# 22-TimingConnections.net
KiCad netlist of a schematic drawn in Altium Designer
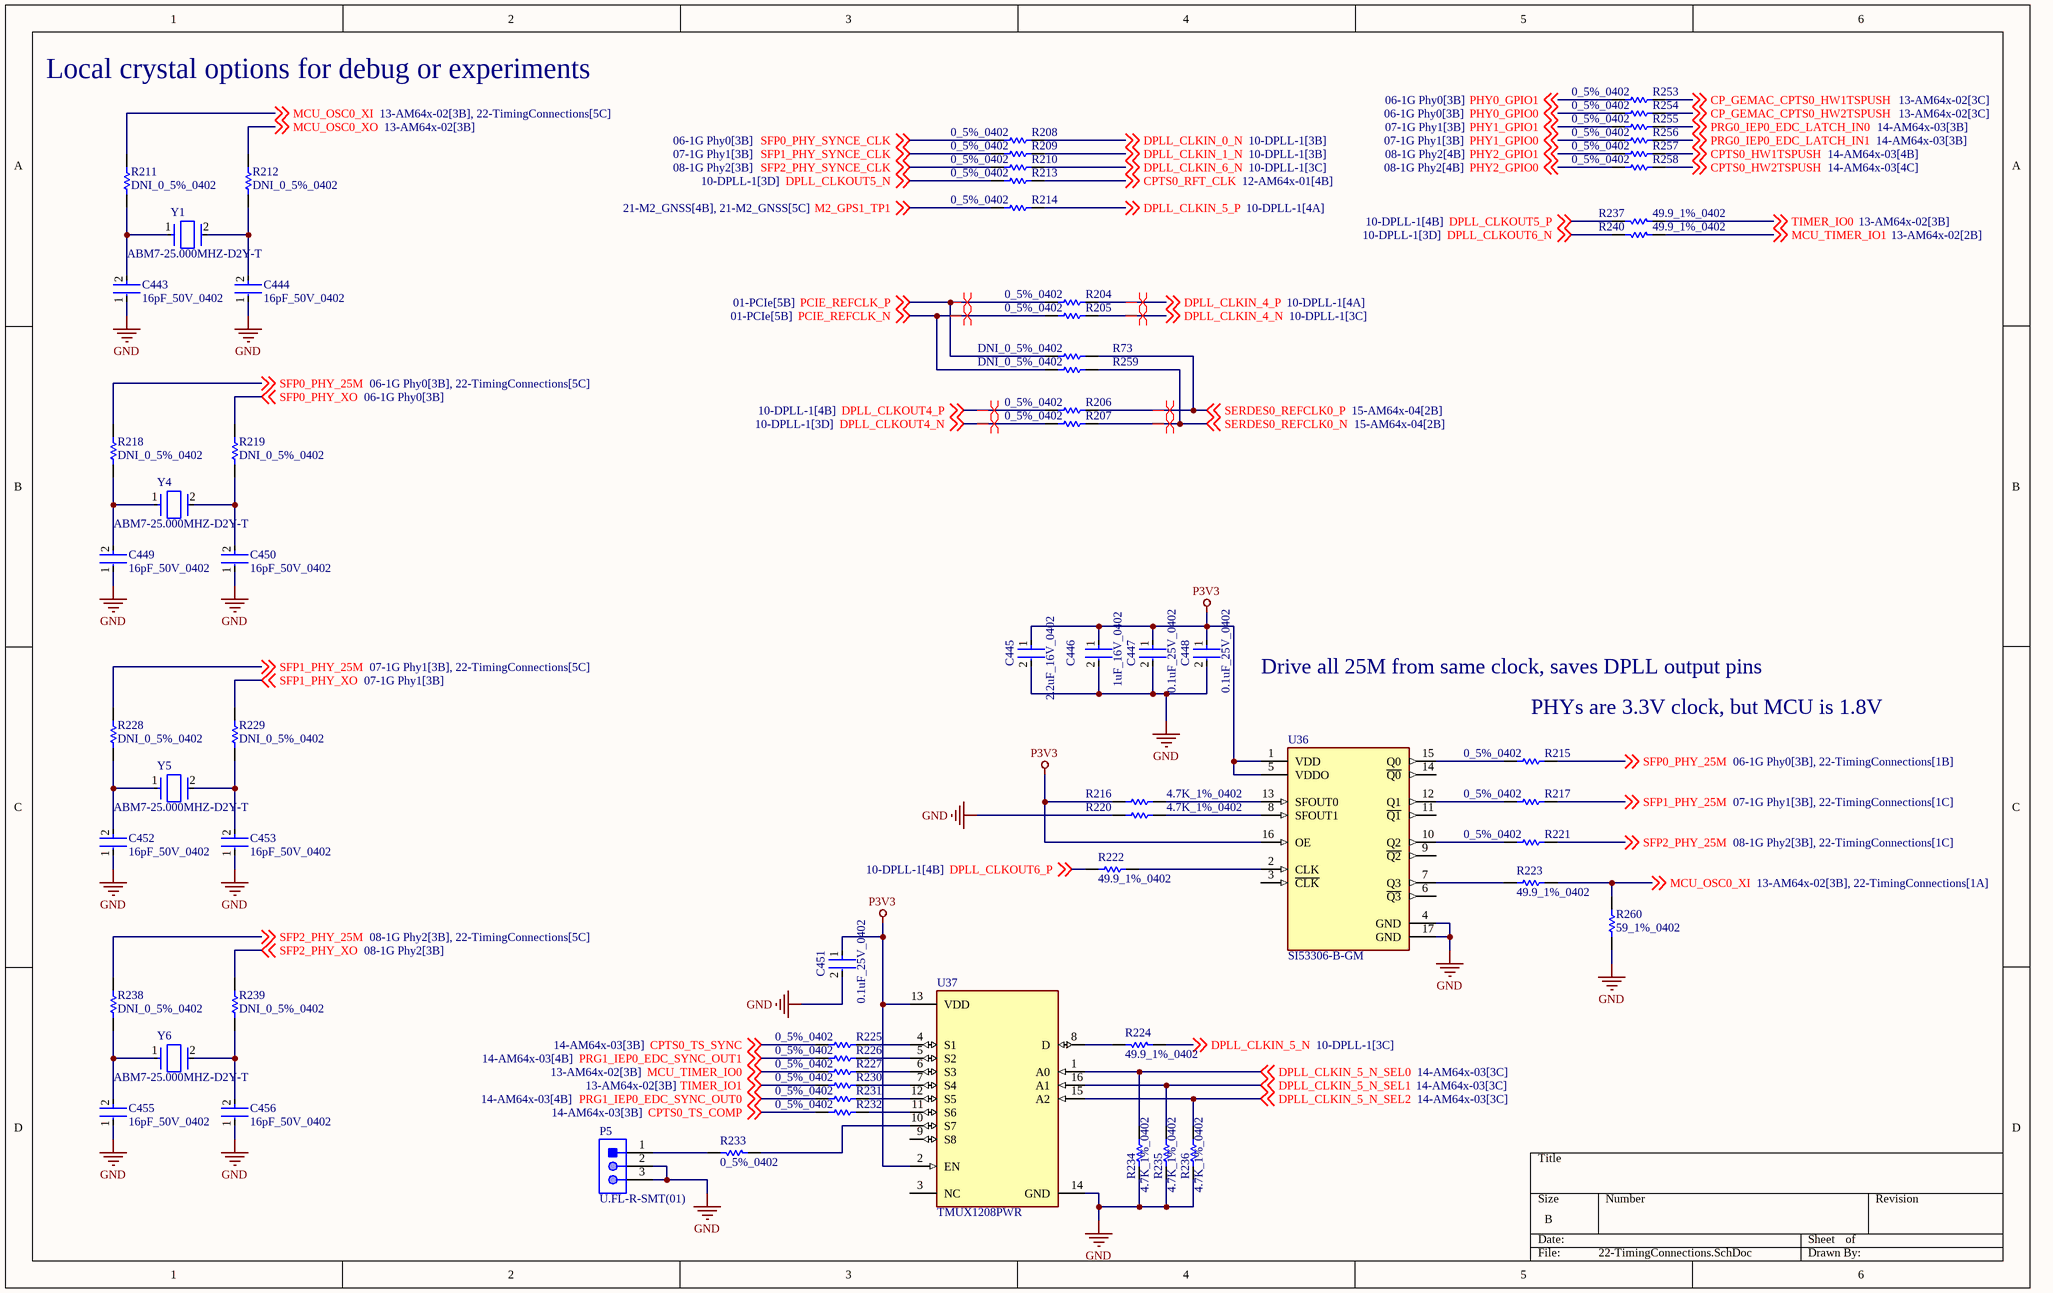
[diagram p0: 22-TimingConnections.SchDoc]

(export (version "E")
  (design (tool "Eeschema 10.0.6"))
  (components
    (comp (ref "C443")
      (value "16pF_50V_0402")
      (footprint "FP-CBR04C-MFG")
      (description "CAP CER 16PF 50V C0G/NP0 0402")
      (fields (field (name "MANUFACTURER") "KEMET") (field (name "TOLERANCE") "0.05"))
      (libsource (lib "Altium Content Vault") (part "236180d848d6139a670b325ea6854c9"))
    )
    (comp (ref "C444")
      (value "16pF_50V_0402")
      (footprint "FP-CBR04C-MFG")
      (description "CAP CER 16PF 50V C0G/NP0 0402")
      (fields (field (name "MANUFACTURER") "KEMET") (field (name "TOLERANCE") "0.05"))
      (libsource (lib "Altium Content Vault") (part "236180d848d6139a670b325ea6854c9"))
    )
    (comp (ref "C445")
      (value "2.2uF_16V_0402")
      (footprint "FP-C1005-050-0_05-IPC_A")
      (description "Multilayer Ceramic Capacitors 2.2μF ±10% 16V X5R SMD 0402")
      (fields (field (name "TOLERANCE") "10%"))
      (libsource (lib "Altium Content Vault") (part "b4654b650e69147ec39a6b967a45e02"))
    )
    (comp (ref "C446")
      (value "1uF_16V_0402")
      (footprint "FP-0402-L_1_0_0_05-W_0_5-IPC_A")
      (description "None")
      (fields (field (name "TOLERANCE") "10%"))
      (libsource (lib "Altium Content Vault") (part "b4654b650e69147ec39a6b967a45e02"))
    )
    (comp (ref "C447")
      (value "0.1uF_25V_0402")
      (footprint "FP-0402-L_1_0_1-W_0_5_0_1-IPC_C")
      (description "General Purpose Ceramic Capacitor, 0402, 100nF, 10%, X7R, 15%, 25V")
      (fields (field (name "VOLTAGE") "25V") (field (name "TOLERANCE") "10%"))
      (libsource (lib "Altium Content Vault") (part "b4654b650e69147ec39a6b967a45e02"))
    )
    (comp (ref "C448")
      (value "0.1uF_25V_0402")
      (footprint "FP-0402-L_1_0_1-W_0_5_0_1-IPC_C")
      (description "General Purpose Ceramic Capacitor, 0402, 100nF, 10%, X7R, 15%, 25V")
      (fields (field (name "VOLTAGE") "25V") (field (name "TOLERANCE") "10%"))
      (libsource (lib "Altium Content Vault") (part "b4654b650e69147ec39a6b967a45e02"))
    )
    (comp (ref "C449")
      (value "16pF_50V_0402")
      (footprint "FP-CBR04C-MFG")
      (description "CAP CER 16PF 50V C0G/NP0 0402")
      (fields (field (name "MANUFACTURER") "KEMET") (field (name "TOLERANCE") "0.05"))
      (libsource (lib "Altium Content Vault") (part "236180d848d6139a670b325ea6854c9"))
    )
    (comp (ref "C450")
      (value "16pF_50V_0402")
      (footprint "FP-CBR04C-MFG")
      (description "CAP CER 16PF 50V C0G/NP0 0402")
      (fields (field (name "MANUFACTURER") "KEMET") (field (name "TOLERANCE") "0.05"))
      (libsource (lib "Altium Content Vault") (part "236180d848d6139a670b325ea6854c9"))
    )
    (comp (ref "C451")
      (value "0.1uF_25V_0402")
      (footprint "FP-0402-L_1_0_1-W_0_5_0_1-IPC_C")
      (description "General Purpose Ceramic Capacitor, 0402, 100nF, 10%, X7R, 15%, 25V")
      (fields (field (name "VOLTAGE") "25V") (field (name "TOLERANCE") "10%"))
      (libsource (lib "Altium Content Vault") (part "b4654b650e69147ec39a6b967a45e02"))
    )
    (comp (ref "C452")
      (value "16pF_50V_0402")
      (footprint "FP-CBR04C-MFG")
      (description "CAP CER 16PF 50V C0G/NP0 0402")
      (fields (field (name "MANUFACTURER") "KEMET") (field (name "TOLERANCE") "0.05"))
      (libsource (lib "Altium Content Vault") (part "236180d848d6139a670b325ea6854c9"))
    )
    (comp (ref "C453")
      (value "16pF_50V_0402")
      (footprint "FP-CBR04C-MFG")
      (description "CAP CER 16PF 50V C0G/NP0 0402")
      (fields (field (name "MANUFACTURER") "KEMET") (field (name "TOLERANCE") "0.05"))
      (libsource (lib "Altium Content Vault") (part "236180d848d6139a670b325ea6854c9"))
    )
    (comp (ref "C455")
      (value "16pF_50V_0402")
      (footprint "FP-CBR04C-MFG")
      (description "CAP CER 16PF 50V C0G/NP0 0402")
      (fields (field (name "MANUFACTURER") "KEMET") (field (name "TOLERANCE") "0.05"))
      (libsource (lib "Altium Content Vault") (part "236180d848d6139a670b325ea6854c9"))
    )
    (comp (ref "C456")
      (value "16pF_50V_0402")
      (footprint "FP-CBR04C-MFG")
      (description "CAP CER 16PF 50V C0G/NP0 0402")
      (fields (field (name "MANUFACTURER") "KEMET") (field (name "TOLERANCE") "0.05"))
      (libsource (lib "Altium Content Vault") (part "236180d848d6139a670b325ea6854c9"))
    )
    (comp (ref "P5")
      (value "U.FL-R-SMT(01)")
      (footprint "HRS-U.FL-R-SMT(10)_V")
      (description "CONN RECPT ULTRA-MINI COAX SMD")
      (fields (field (name "MANUFACTURER") "Hirose Electric") (field (name "APPROVAL CATEGORY") "UL94V-0"))
      (libsource (lib "Altium Content Vault") (part "CN-1P-M-R3"))
    )
    (comp (ref "R73")
      (value "DNI_0_5%_0402")
      (footprint "RESC1005X40X25LL10T10")
      (fields (field (name "MANUFACTURER") "KOA Speer") (field (name "PART NUMBER") "RK73Z1ETTP"))
      (libsource (lib "Altium Content Vault") (part "RES"))
    )
    (comp (ref "R204")
      (value "0_5%_0402")
      (footprint "RESC1005X40X25LL10T10")
      (fields (field (name "MANUFACTURER") "KOA Speer") (field (name "PART NUMBER") "RK73Z1ETTP"))
      (libsource (lib "Altium Content Vault") (part "RES"))
    )
    (comp (ref "R205")
      (value "0_5%_0402")
      (footprint "RESC1005X40X25LL10T10")
      (fields (field (name "MANUFACTURER") "KOA Speer") (field (name "PART NUMBER") "RK73Z1ETTP"))
      (libsource (lib "Altium Content Vault") (part "RES"))
    )
    (comp (ref "R206")
      (value "0_5%_0402")
      (footprint "RESC1005X40X25LL10T10")
      (fields (field (name "MANUFACTURER") "KOA Speer") (field (name "PART NUMBER") "RK73Z1ETTP"))
      (libsource (lib "Altium Content Vault") (part "RES"))
    )
    (comp (ref "R207")
      (value "0_5%_0402")
      (footprint "RESC1005X40X25LL10T10")
      (fields (field (name "MANUFACTURER") "KOA Speer") (field (name "PART NUMBER") "RK73Z1ETTP"))
      (libsource (lib "Altium Content Vault") (part "RES"))
    )
    (comp (ref "R208")
      (value "0_5%_0402")
      (footprint "RESC1005X40X25LL10T10")
      (fields (field (name "MANUFACTURER") "KOA Speer") (field (name "PART NUMBER") "RK73Z1ETTP"))
      (libsource (lib "Altium Content Vault") (part "RES"))
    )
    (comp (ref "R209")
      (value "0_5%_0402")
      (footprint "RESC1005X40X25LL10T10")
      (fields (field (name "MANUFACTURER") "KOA Speer") (field (name "PART NUMBER") "RK73Z1ETTP"))
      (libsource (lib "Altium Content Vault") (part "RES"))
    )
    (comp (ref "R210")
      (value "0_5%_0402")
      (footprint "RESC1005X40X25LL10T10")
      (fields (field (name "MANUFACTURER") "KOA Speer") (field (name "PART NUMBER") "RK73Z1ETTP"))
      (libsource (lib "Altium Content Vault") (part "RES"))
    )
    (comp (ref "R211")
      (value "DNI_0_5%_0402")
      (footprint "RESC1005X40X25LL10T10")
      (fields (field (name "MANUFACTURER") "KOA Speer") (field (name "PART NUMBER") "RK73Z1ETTP"))
      (libsource (lib "Altium Content Vault") (part "RES"))
    )
    (comp (ref "R212")
      (value "DNI_0_5%_0402")
      (footprint "RESC1005X40X25LL10T10")
      (fields (field (name "MANUFACTURER") "KOA Speer") (field (name "PART NUMBER") "RK73Z1ETTP"))
      (libsource (lib "Altium Content Vault") (part "RES"))
    )
    (comp (ref "R213")
      (value "0_5%_0402")
      (footprint "RESC1005X40X25LL10T10")
      (fields (field (name "MANUFACTURER") "KOA Speer") (field (name "PART NUMBER") "RK73Z1ETTP"))
      (libsource (lib "Altium Content Vault") (part "RES"))
    )
    (comp (ref "R214")
      (value "0_5%_0402")
      (footprint "RESC1005X40X25LL10T10")
      (fields (field (name "MANUFACTURER") "KOA Speer") (field (name "PART NUMBER") "RK73Z1ETTP"))
      (libsource (lib "Altium Content Vault") (part "RES"))
    )
    (comp (ref "R215")
      (value "0_5%_0402")
      (footprint "RESC1005X40X25LL10T10")
      (fields (field (name "MANUFACTURER") "KOA Speer") (field (name "PART NUMBER") "RK73Z1ETTP"))
      (libsource (lib "Altium Content Vault") (part "RES"))
    )
    (comp (ref "R216")
      (value "4.7K_1%_0402")
      (footprint "RESC1005X40X25NL10T10")
      (fields (field (name "MANUFACTURER") "Bourns") (field (name "PART NUMBER") "CR0402-FX-4701GLF"))
      (libsource (lib "Altium Content Vault") (part "RES"))
    )
    (comp (ref "R217")
      (value "0_5%_0402")
      (footprint "RESC1005X40X25LL10T10")
      (fields (field (name "MANUFACTURER") "KOA Speer") (field (name "PART NUMBER") "RK73Z1ETTP"))
      (libsource (lib "Altium Content Vault") (part "RES"))
    )
    (comp (ref "R218")
      (value "DNI_0_5%_0402")
      (footprint "RESC1005X40X25LL10T10")
      (fields (field (name "MANUFACTURER") "KOA Speer") (field (name "PART NUMBER") "RK73Z1ETTP"))
      (libsource (lib "Altium Content Vault") (part "RES"))
    )
    (comp (ref "R219")
      (value "DNI_0_5%_0402")
      (footprint "RESC1005X40X25LL10T10")
      (fields (field (name "MANUFACTURER") "KOA Speer") (field (name "PART NUMBER") "RK73Z1ETTP"))
      (libsource (lib "Altium Content Vault") (part "RES"))
    )
    (comp (ref "R220")
      (value "4.7K_1%_0402")
      (footprint "RESC1005X40X25NL10T10")
      (fields (field (name "MANUFACTURER") "Bourns") (field (name "PART NUMBER") "CR0402-FX-4701GLF"))
      (libsource (lib "Altium Content Vault") (part "RES"))
    )
    (comp (ref "R221")
      (value "0_5%_0402")
      (footprint "RESC1005X40X25LL10T10")
      (fields (field (name "MANUFACTURER") "KOA Speer") (field (name "PART NUMBER") "RK73Z1ETTP"))
      (libsource (lib "Altium Content Vault") (part "RES"))
    )
    (comp (ref "R222")
      (value "49.9_1%_0402")
      (footprint "RESC1005X40X25NL10T10")
      (fields (field (name "PART NUMBER") "RK73H1ETTP49R9F") (field (name "MANUFACTURER") "KOA Speer"))
      (libsource (lib "Altium Content Vault") (part "RES"))
    )
    (comp (ref "R223")
      (value "49.9_1%_0402")
      (footprint "RESC1005X40X25NL10T10")
      (fields (field (name "PART NUMBER") "RK73H1ETTP49R9F") (field (name "MANUFACTURER") "KOA Speer"))
      (libsource (lib "Altium Content Vault") (part "RES"))
    )
    (comp (ref "R224")
      (value "49.9_1%_0402")
      (footprint "RESC1005X40X25NL10T10")
      (fields (field (name "PART NUMBER") "RK73H1ETTP49R9F") (field (name "MANUFACTURER") "KOA Speer"))
      (libsource (lib "Altium Content Vault") (part "RES"))
    )
    (comp (ref "R225")
      (value "0_5%_0402")
      (footprint "RESC1005X40X25LL10T10")
      (fields (field (name "MANUFACTURER") "KOA Speer") (field (name "PART NUMBER") "RK73Z1ETTP"))
      (libsource (lib "Altium Content Vault") (part "RES"))
    )
    (comp (ref "R226")
      (value "0_5%_0402")
      (footprint "RESC1005X40X25LL10T10")
      (fields (field (name "MANUFACTURER") "KOA Speer") (field (name "PART NUMBER") "RK73Z1ETTP"))
      (libsource (lib "Altium Content Vault") (part "RES"))
    )
    (comp (ref "R227")
      (value "0_5%_0402")
      (footprint "RESC1005X40X25LL10T10")
      (fields (field (name "MANUFACTURER") "KOA Speer") (field (name "PART NUMBER") "RK73Z1ETTP"))
      (libsource (lib "Altium Content Vault") (part "RES"))
    )
    (comp (ref "R228")
      (value "DNI_0_5%_0402")
      (footprint "RESC1005X40X25LL10T10")
      (fields (field (name "MANUFACTURER") "KOA Speer") (field (name "PART NUMBER") "RK73Z1ETTP"))
      (libsource (lib "Altium Content Vault") (part "RES"))
    )
    (comp (ref "R229")
      (value "DNI_0_5%_0402")
      (footprint "RESC1005X40X25LL10T10")
      (fields (field (name "MANUFACTURER") "KOA Speer") (field (name "PART NUMBER") "RK73Z1ETTP"))
      (libsource (lib "Altium Content Vault") (part "RES"))
    )
    (comp (ref "R230")
      (value "0_5%_0402")
      (footprint "RESC1005X40X25LL10T10")
      (fields (field (name "MANUFACTURER") "KOA Speer") (field (name "PART NUMBER") "RK73Z1ETTP"))
      (libsource (lib "Altium Content Vault") (part "RES"))
    )
    (comp (ref "R231")
      (value "0_5%_0402")
      (footprint "RESC1005X40X25LL10T10")
      (fields (field (name "MANUFACTURER") "KOA Speer") (field (name "PART NUMBER") "RK73Z1ETTP"))
      (libsource (lib "Altium Content Vault") (part "RES"))
    )
    (comp (ref "R232")
      (value "0_5%_0402")
      (footprint "RESC1005X40X25LL10T10")
      (fields (field (name "MANUFACTURER") "KOA Speer") (field (name "PART NUMBER") "RK73Z1ETTP"))
      (libsource (lib "Altium Content Vault") (part "RES"))
    )
    (comp (ref "R233")
      (value "0_5%_0402")
      (footprint "RESC1005X40X25LL10T10")
      (fields (field (name "MANUFACTURER") "KOA Speer") (field (name "PART NUMBER") "RK73Z1ETTP"))
      (libsource (lib "Altium Content Vault") (part "RES"))
    )
    (comp (ref "R234")
      (value "4.7K_1%_0402")
      (footprint "RESC1005X40X25NL10T10")
      (fields (field (name "MANUFACTURER") "Bourns") (field (name "PART NUMBER") "CR0402-FX-4701GLF"))
      (libsource (lib "Altium Content Vault") (part "RES"))
    )
    (comp (ref "R235")
      (value "4.7K_1%_0402")
      (footprint "RESC1005X40X25NL10T10")
      (fields (field (name "MANUFACTURER") "Bourns") (field (name "PART NUMBER") "CR0402-FX-4701GLF"))
      (libsource (lib "Altium Content Vault") (part "RES"))
    )
    (comp (ref "R236")
      (value "4.7K_1%_0402")
      (footprint "RESC1005X40X25NL10T10")
      (fields (field (name "MANUFACTURER") "Bourns") (field (name "PART NUMBER") "CR0402-FX-4701GLF"))
      (libsource (lib "Altium Content Vault") (part "RES"))
    )
    (comp (ref "R237")
      (value "49.9_1%_0402")
      (footprint "RESC1005X40X25NL10T10")
      (fields (field (name "PART NUMBER") "RK73H1ETTP49R9F") (field (name "MANUFACTURER") "KOA Speer"))
      (libsource (lib "Altium Content Vault") (part "RES"))
    )
    (comp (ref "R238")
      (value "DNI_0_5%_0402")
      (footprint "RESC1005X40X25LL10T10")
      (fields (field (name "MANUFACTURER") "KOA Speer") (field (name "PART NUMBER") "RK73Z1ETTP"))
      (libsource (lib "Altium Content Vault") (part "RES"))
    )
    (comp (ref "R239")
      (value "DNI_0_5%_0402")
      (footprint "RESC1005X40X25LL10T10")
      (fields (field (name "MANUFACTURER") "KOA Speer") (field (name "PART NUMBER") "RK73Z1ETTP"))
      (libsource (lib "Altium Content Vault") (part "RES"))
    )
    (comp (ref "R240")
      (value "49.9_1%_0402")
      (footprint "RESC1005X40X25NL10T10")
      (fields (field (name "PART NUMBER") "RK73H1ETTP49R9F") (field (name "MANUFACTURER") "KOA Speer"))
      (libsource (lib "Altium Content Vault") (part "RES"))
    )
    (comp (ref "R253")
      (value "0_5%_0402")
      (footprint "RESC1005X40X25LL10T10")
      (fields (field (name "MANUFACTURER") "KOA Speer") (field (name "PART NUMBER") "RK73Z1ETTP"))
      (libsource (lib "Altium Content Vault") (part "RES"))
    )
    (comp (ref "R254")
      (value "0_5%_0402")
      (footprint "RESC1005X40X25LL10T10")
      (fields (field (name "MANUFACTURER") "KOA Speer") (field (name "PART NUMBER") "RK73Z1ETTP"))
      (libsource (lib "Altium Content Vault") (part "RES"))
    )
    (comp (ref "R255")
      (value "0_5%_0402")
      (footprint "RESC1005X40X25LL10T10")
      (fields (field (name "MANUFACTURER") "KOA Speer") (field (name "PART NUMBER") "RK73Z1ETTP"))
      (libsource (lib "Altium Content Vault") (part "RES"))
    )
    (comp (ref "R256")
      (value "0_5%_0402")
      (footprint "RESC1005X40X25LL10T10")
      (fields (field (name "MANUFACTURER") "KOA Speer") (field (name "PART NUMBER") "RK73Z1ETTP"))
      (libsource (lib "Altium Content Vault") (part "RES"))
    )
    (comp (ref "R257")
      (value "0_5%_0402")
      (footprint "RESC1005X40X25LL10T10")
      (fields (field (name "MANUFACTURER") "KOA Speer") (field (name "PART NUMBER") "RK73Z1ETTP"))
      (libsource (lib "Altium Content Vault") (part "RES"))
    )
    (comp (ref "R258")
      (value "0_5%_0402")
      (footprint "RESC1005X40X25LL10T10")
      (fields (field (name "MANUFACTURER") "KOA Speer") (field (name "PART NUMBER") "RK73Z1ETTP"))
      (libsource (lib "Altium Content Vault") (part "RES"))
    )
    (comp (ref "R259")
      (value "DNI_0_5%_0402")
      (footprint "RESC1005X40X25LL10T10")
      (fields (field (name "MANUFACTURER") "KOA Speer") (field (name "PART NUMBER") "RK73Z1ETTP"))
      (libsource (lib "Altium Content Vault") (part "RES"))
    )
    (comp (ref "R260")
      (value "59_1%_0402")
      (footprint "RESC1005X40X25ML10T10")
      (fields (field (name "MANUFACTURER") "KOA Speer") (field (name "PART NUMBER") "RK73H1ETTP59R0F"))
      (libsource (lib "Altium Content Vault") (part "RES"))
    )
    (comp (ref "U36")
      (value "SI53306-B-GM")
      (footprint "FP-SI53306-B-GM-MFG")
      (description "IC BUFFER/LEVEL XLATOR 1:4 16QFN")
      (fields
        (field (name "OCTOPART") "https://octopart.com/si53306-b-gm-silicon+labs-29690230")
        (field (name "MANUFACTURER") "Silicon Labs")
      )
      (libsource (lib "Altium Content Vault") (part "4a651b1158e12a4d20662f1ed0d1947"))
    )
    (comp (ref "U37")
      (value "TMUX1208PWR")
      (footprint "FP-PW0016A-IPC_A")
      (description "IC SWITCH SINGLE 16TSSOP")
      (libsource (lib "Altium Content Vault") (part "3fc1eebd4caa5623a46538ca285a60d"))
    )
    (comp (ref "Y1")
      (value "ABM7-25.000MHZ-D2Y-T")
      (footprint "FP-ABM7-MFG")
      (description "Crystal 25MHz ±20ppm 18pF SMD-2 6mm x 3.5mm")
      (fields (field (name "TOLERANCE") "20ppm"))
      (libsource (lib "Altium Content Vault") (part "c23a69dc6c9e2f18f2079038eb95dd1"))
    )
    (comp (ref "Y4")
      (value "ABM7-25.000MHZ-D2Y-T")
      (footprint "FP-ABM7-MFG")
      (description "Crystal 25MHz ±20ppm 18pF SMD-2 6mm x 3.5mm")
      (fields (field (name "TOLERANCE") "20ppm"))
      (libsource (lib "Altium Content Vault") (part "c23a69dc6c9e2f18f2079038eb95dd1"))
    )
    (comp (ref "Y5")
      (value "ABM7-25.000MHZ-D2Y-T")
      (footprint "FP-ABM7-MFG")
      (description "Crystal 25MHz ±20ppm 18pF SMD-2 6mm x 3.5mm")
      (fields (field (name "TOLERANCE") "20ppm"))
      (libsource (lib "Altium Content Vault") (part "c23a69dc6c9e2f18f2079038eb95dd1"))
    )
    (comp (ref "Y6")
      (value "ABM7-25.000MHZ-D2Y-T")
      (footprint "FP-ABM7-MFG")
      (description "Crystal 25MHz ±20ppm 18pF SMD-2 6mm x 3.5mm")
      (fields (field (name "TOLERANCE") "20ppm"))
      (libsource (lib "Altium Content Vault") (part "c23a69dc6c9e2f18f2079038eb95dd1"))
    )
  )
  (nets
    (net (code "1") (name "CPTS0_HW1TSPUSH") (class "Default")
      (node (ref "R257") (pin "2") (pinfunction "2_2") (pintype "passive"))
    )
    (net (code "2") (name "CPTS0_HW2TSPUSH") (class "Default")
      (node (ref "R258") (pin "2") (pinfunction "2_2") (pintype "passive"))
    )
    (net (code "3") (name "CPTS0_RFT_CLK") (class "Default")
      (node (ref "R213") (pin "2") (pinfunction "2_2") (pintype "passive"))
    )
    (net (code "4") (name "CPTS0_TS_COMP") (class "Default")
      (node (ref "R232") (pin "1") (pinfunction "1_1") (pintype "passive"))
    )
    (net (code "5") (name "CPTS0_TS_SYNC") (class "Default")
      (node (ref "R225") (pin "1") (pinfunction "1_1") (pintype "passive"))
    )
    (net (code "6") (name "CP_GEMAC_CPTS0_HW1TSPUSH") (class "Default")
      (node (ref "R253") (pin "2") (pinfunction "2_2") (pintype "passive"))
    )
    (net (code "7") (name "CP_GEMAC_CPTS0_HW2TSPUSH") (class "Default")
      (node (ref "R254") (pin "2") (pinfunction "2_2") (pintype "passive"))
    )
    (net (code "8") (name "DPLL_CLKIN_0_N") (class "Default")
      (node (ref "R208") (pin "2") (pinfunction "2_2") (pintype "passive"))
    )
    (net (code "9") (name "DPLL_CLKIN_1_N") (class "Default")
      (node (ref "R209") (pin "2") (pinfunction "2_2") (pintype "passive"))
    )
    (net (code "10") (name "DPLL_CLKIN_4_N") (class "Default")
      (node (ref "R205") (pin "2") (pinfunction "2_2") (pintype "passive"))
    )
    (net (code "11") (name "DPLL_CLKIN_4_P") (class "Default")
      (node (ref "R204") (pin "2") (pinfunction "2_2") (pintype "passive"))
    )
    (net (code "12") (name "DPLL_CLKIN_5_N") (class "Default")
      (node (ref "R224") (pin "1") (pinfunction "1_1") (pintype "passive"))
    )
    (net (code "13") (name "DPLL_CLKIN_5_N_SEL0") (class "Default")
      (node (ref "R234") (pin "1") (pinfunction "1_1") (pintype "passive"))
      (node (ref "U37") (pin "1") (pinfunction "A0_1") (pintype "input"))
    )
    (net (code "14") (name "DPLL_CLKIN_5_N_SEL1") (class "Default")
      (node (ref "R235") (pin "1") (pinfunction "1_1") (pintype "passive"))
      (node (ref "U37") (pin "16") (pinfunction "A1_16") (pintype "input"))
    )
    (net (code "15") (name "DPLL_CLKIN_5_N_SEL2") (class "Default")
      (node (ref "R236") (pin "1") (pinfunction "1_1") (pintype "passive"))
      (node (ref "U37") (pin "15") (pinfunction "A2_15") (pintype "input"))
    )
    (net (code "16") (name "DPLL_CLKIN_5_P") (class "Default")
      (node (ref "R214") (pin "2") (pinfunction "2_2") (pintype "passive"))
    )
    (net (code "17") (name "DPLL_CLKIN_6_N") (class "Default")
      (node (ref "R210") (pin "2") (pinfunction "2_2") (pintype "passive"))
    )
    (net (code "18") (name "DPLL_CLKOUT4_N") (class "Default")
      (node (ref "R207") (pin "1") (pinfunction "1_1") (pintype "passive"))
    )
    (net (code "19") (name "DPLL_CLKOUT4_P") (class "Default")
      (node (ref "R206") (pin "1") (pinfunction "1_1") (pintype "passive"))
    )
    (net (code "20") (name "DPLL_CLKOUT5_N") (class "Default")
      (node (ref "R213") (pin "1") (pinfunction "1_1") (pintype "passive"))
    )
    (net (code "21") (name "DPLL_CLKOUT5_P") (class "Default")
      (node (ref "R237") (pin "2") (pinfunction "2_2") (pintype "passive"))
    )
    (net (code "22") (name "DPLL_CLKOUT6_N") (class "Default")
      (node (ref "R240") (pin "2") (pinfunction "2_2") (pintype "passive"))
    )
    (net (code "23") (name "DPLL_CLKOUT6_P") (class "Default")
      (node (ref "R222") (pin "1") (pinfunction "1_1") (pintype "passive"))
    )
    (net (code "24") (name "GND") (class "Default")
      (node (ref "C443") (pin "1") (pinfunction "1_1") (pintype "passive"))
      (node (ref "C444") (pin "1") (pinfunction "1_1") (pintype "passive"))
      (node (ref "C445") (pin "2") (pinfunction "2_2") (pintype "passive"))
      (node (ref "C446") (pin "2") (pinfunction "2_2") (pintype "passive"))
      (node (ref "C447") (pin "2") (pinfunction "2_2") (pintype "passive"))
      (node (ref "C448") (pin "2") (pinfunction "2_2") (pintype "passive"))
      (node (ref "C449") (pin "1") (pinfunction "1_1") (pintype "passive"))
      (node (ref "C450") (pin "1") (pinfunction "1_1") (pintype "passive"))
      (node (ref "C451") (pin "2") (pinfunction "2_2") (pintype "passive"))
      (node (ref "C452") (pin "1") (pinfunction "1_1") (pintype "passive"))
      (node (ref "C453") (pin "1") (pinfunction "1_1") (pintype "passive"))
      (node (ref "C455") (pin "1") (pinfunction "1_1") (pintype "passive"))
      (node (ref "C456") (pin "1") (pinfunction "1_1") (pintype "passive"))
      (node (ref "P5") (pin "2") (pinfunction "2_2") (pintype "passive"))
      (node (ref "P5") (pin "3") (pinfunction "3_3") (pintype "passive"))
      (node (ref "R220") (pin "2") (pinfunction "2_2") (pintype "passive"))
      (node (ref "R234") (pin "2") (pinfunction "2_2") (pintype "passive"))
      (node (ref "R235") (pin "2") (pinfunction "2_2") (pintype "passive"))
      (node (ref "R236") (pin "2") (pinfunction "2_2") (pintype "passive"))
      (node (ref "R260") (pin "1") (pinfunction "1_1") (pintype "passive"))
      (node (ref "U36") (pin "17") (pinfunction "GND_17") (pintype "power_in"))
      (node (ref "U36") (pin "4") (pinfunction "GND_4") (pintype "power_in"))
      (node (ref "U37") (pin "14") (pinfunction "GND_14") (pintype "power_in"))
    )
    (net (code "25") (name "M2_GPS1_TP1") (class "Default")
      (node (ref "R214") (pin "1") (pinfunction "1_1") (pintype "passive"))
    )
    (net (code "26") (name "MCU_OSC0_XI") (class "Default")
      (node (ref "R211") (pin "2") (pinfunction "2_2") (pintype "passive"))
      (node (ref "R223") (pin "2") (pinfunction "2_2") (pintype "passive"))
      (node (ref "R260") (pin "2") (pinfunction "2_2") (pintype "passive"))
    )
    (net (code "27") (name "MCU_OSC0_XO") (class "Default")
      (node (ref "R212") (pin "2") (pinfunction "2_2") (pintype "passive"))
    )
    (net (code "28") (name "MCU_TIMER_IO0") (class "Default")
      (node (ref "R227") (pin "1") (pinfunction "1_1") (pintype "passive"))
    )
    (net (code "29") (name "MCU_TIMER_IO1") (class "Default")
      (node (ref "R240") (pin "1") (pinfunction "1_1") (pintype "passive"))
    )
    (net (code "30") (name "Net-(C443-Pad2)") (class "Default")
      (node (ref "C443") (pin "2") (pinfunction "2_2") (pintype "passive"))
      (node (ref "R211") (pin "1") (pinfunction "1_1") (pintype "passive"))
      (node (ref "Y1") (pin "1") (pinfunction "1_1") (pintype "passive"))
    )
    (net (code "31") (name "Net-(C444-Pad2)") (class "Default")
      (node (ref "C444") (pin "2") (pinfunction "2_2") (pintype "passive"))
      (node (ref "R212") (pin "1") (pinfunction "1_1") (pintype "passive"))
      (node (ref "Y1") (pin "2") (pinfunction "2_2") (pintype "passive"))
    )
    (net (code "32") (name "Net-(C449-Pad2)") (class "Default")
      (node (ref "C449") (pin "2") (pinfunction "2_2") (pintype "passive"))
      (node (ref "R218") (pin "1") (pinfunction "1_1") (pintype "passive"))
      (node (ref "Y4") (pin "1") (pinfunction "1_1") (pintype "passive"))
    )
    (net (code "33") (name "Net-(C450-Pad2)") (class "Default")
      (node (ref "C450") (pin "2") (pinfunction "2_2") (pintype "passive"))
      (node (ref "R219") (pin "1") (pinfunction "1_1") (pintype "passive"))
      (node (ref "Y4") (pin "2") (pinfunction "2_2") (pintype "passive"))
    )
    (net (code "34") (name "Net-(C452-Pad2)") (class "Default")
      (node (ref "C452") (pin "2") (pinfunction "2_2") (pintype "passive"))
      (node (ref "R228") (pin "1") (pinfunction "1_1") (pintype "passive"))
      (node (ref "Y5") (pin "1") (pinfunction "1_1") (pintype "passive"))
    )
    (net (code "35") (name "Net-(C453-Pad2)") (class "Default")
      (node (ref "C453") (pin "2") (pinfunction "2_2") (pintype "passive"))
      (node (ref "R229") (pin "1") (pinfunction "1_1") (pintype "passive"))
      (node (ref "Y5") (pin "2") (pinfunction "2_2") (pintype "passive"))
    )
    (net (code "36") (name "Net-(C455-Pad2)") (class "Default")
      (node (ref "C455") (pin "2") (pinfunction "2_2") (pintype "passive"))
      (node (ref "R238") (pin "1") (pinfunction "1_1") (pintype "passive"))
      (node (ref "Y6") (pin "1") (pinfunction "1_1") (pintype "passive"))
    )
    (net (code "37") (name "Net-(C456-Pad2)") (class "Default")
      (node (ref "C456") (pin "2") (pinfunction "2_2") (pintype "passive"))
      (node (ref "R239") (pin "1") (pinfunction "1_1") (pintype "passive"))
      (node (ref "Y6") (pin "2") (pinfunction "2_2") (pintype "passive"))
    )
    (net (code "38") (name "Net-(P5-Pad1)") (class "Default")
      (node (ref "P5") (pin "1") (pinfunction "1_1") (pintype "passive"))
      (node (ref "R233") (pin "2") (pinfunction "2_2") (pintype "passive"))
    )
    (net (code "39") (name "Net-(U36-CLK)") (class "Default")
      (node (ref "R222") (pin "2") (pinfunction "2_2") (pintype "passive"))
      (node (ref "U36") (pin "2") (pinfunction "CLK_2") (pintype "input"))
    )
    (net (code "40") (name "Net-(U36-Q0)") (class "Default")
      (node (ref "R215") (pin "1") (pinfunction "1_1") (pintype "passive"))
      (node (ref "U36") (pin "15") (pinfunction "Q0_15") (pintype "output"))
    )
    (net (code "41") (name "Net-(U36-Q1)") (class "Default")
      (node (ref "R217") (pin "1") (pinfunction "1_1") (pintype "passive"))
      (node (ref "U36") (pin "12") (pinfunction "Q1_12") (pintype "output"))
    )
    (net (code "42") (name "Net-(U36-Q2)") (class "Default")
      (node (ref "R221") (pin "1") (pinfunction "1_1") (pintype "passive"))
      (node (ref "U36") (pin "10") (pinfunction "Q2_10") (pintype "output"))
    )
    (net (code "43") (name "Net-(U36-Q3)") (class "Default")
      (node (ref "R223") (pin "1") (pinfunction "1_1") (pintype "passive"))
      (node (ref "U36") (pin "7") (pinfunction "Q3_7") (pintype "output"))
    )
    (net (code "44") (name "Net-(U36-SFOUT0)") (class "Default")
      (node (ref "R216") (pin "1") (pinfunction "1_1") (pintype "passive"))
      (node (ref "U36") (pin "13") (pinfunction "SFOUT0_13") (pintype "input"))
    )
    (net (code "45") (name "Net-(U36-SFOUT1)") (class "Default")
      (node (ref "R220") (pin "1") (pinfunction "1_1") (pintype "passive"))
      (node (ref "U36") (pin "8") (pinfunction "SFOUT1_8") (pintype "input"))
    )
    (net (code "46") (name "Net-(U37-D)") (class "Default")
      (node (ref "R224") (pin "2") (pinfunction "2_2") (pintype "passive"))
      (node (ref "U37") (pin "8") (pinfunction "D_8") (pintype "bidirectional"))
    )
    (net (code "47") (name "Net-(U37-S1)") (class "Default")
      (node (ref "R225") (pin "2") (pinfunction "2_2") (pintype "passive"))
      (node (ref "U37") (pin "4") (pinfunction "S1_4") (pintype "bidirectional"))
    )
    (net (code "48") (name "Net-(U37-S2)") (class "Default")
      (node (ref "R226") (pin "2") (pinfunction "2_2") (pintype "passive"))
      (node (ref "U37") (pin "5") (pinfunction "S2_5") (pintype "bidirectional"))
    )
    (net (code "49") (name "Net-(U37-S3)") (class "Default")
      (node (ref "R227") (pin "2") (pinfunction "2_2") (pintype "passive"))
      (node (ref "U37") (pin "6") (pinfunction "S3_6") (pintype "bidirectional"))
    )
    (net (code "50") (name "Net-(U37-S4)") (class "Default")
      (node (ref "R230") (pin "2") (pinfunction "2_2") (pintype "passive"))
      (node (ref "U37") (pin "7") (pinfunction "S4_7") (pintype "bidirectional"))
    )
    (net (code "51") (name "Net-(U37-S5)") (class "Default")
      (node (ref "R231") (pin "2") (pinfunction "2_2") (pintype "passive"))
      (node (ref "U37") (pin "12") (pinfunction "S5_12") (pintype "bidirectional"))
    )
    (net (code "52") (name "Net-(U37-S6)") (class "Default")
      (node (ref "R232") (pin "2") (pinfunction "2_2") (pintype "passive"))
      (node (ref "U37") (pin "11") (pinfunction "S6_11") (pintype "bidirectional"))
    )
    (net (code "53") (name "Net-(U37-S7)") (class "Default")
      (node (ref "R233") (pin "1") (pinfunction "1_1") (pintype "passive"))
      (node (ref "U37") (pin "10") (pinfunction "S7_10") (pintype "bidirectional"))
    )
    (net (code "54") (name "P3V3") (class "Default")
      (node (ref "C445") (pin "1") (pinfunction "1_1") (pintype "passive"))
      (node (ref "C446") (pin "1") (pinfunction "1_1") (pintype "passive"))
      (node (ref "C447") (pin "1") (pinfunction "1_1") (pintype "passive"))
      (node (ref "C448") (pin "1") (pinfunction "1_1") (pintype "passive"))
      (node (ref "C451") (pin "1") (pinfunction "1_1") (pintype "passive"))
      (node (ref "R216") (pin "2") (pinfunction "2_2") (pintype "passive"))
      (node (ref "U36") (pin "1") (pinfunction "VDD_1") (pintype "power_in"))
      (node (ref "U36") (pin "16") (pinfunction "OE_16") (pintype "input"))
      (node (ref "U36") (pin "5") (pinfunction "VDDO_5") (pintype "power_in"))
      (node (ref "U37") (pin "13") (pinfunction "VDD_13") (pintype "power_in"))
      (node (ref "U37") (pin "2") (pinfunction "EN_2") (pintype "input"))
    )
    (net (code "55") (name "PCIE_REFCLK_N") (class "Default")
      (node (ref "R205") (pin "1") (pinfunction "1_1") (pintype "passive"))
      (node (ref "R259") (pin "1") (pinfunction "1_1") (pintype "passive"))
    )
    (net (code "56") (name "PCIE_REFCLK_P") (class "Default")
      (node (ref "R204") (pin "1") (pinfunction "1_1") (pintype "passive"))
      (node (ref "R73") (pin "1") (pinfunction "1_1") (pintype "passive"))
    )
    (net (code "57") (name "PHY0_GPIO0") (class "Default")
      (node (ref "R254") (pin "1") (pinfunction "1_1") (pintype "passive"))
    )
    (net (code "58") (name "PHY0_GPIO1") (class "Default")
      (node (ref "R253") (pin "1") (pinfunction "1_1") (pintype "passive"))
    )
    (net (code "59") (name "PHY1_GPIO0") (class "Default")
      (node (ref "R256") (pin "1") (pinfunction "1_1") (pintype "passive"))
    )
    (net (code "60") (name "PHY1_GPIO1") (class "Default")
      (node (ref "R255") (pin "1") (pinfunction "1_1") (pintype "passive"))
    )
    (net (code "61") (name "PHY2_GPIO0") (class "Default")
      (node (ref "R258") (pin "1") (pinfunction "1_1") (pintype "passive"))
    )
    (net (code "62") (name "PHY2_GPIO1") (class "Default")
      (node (ref "R257") (pin "1") (pinfunction "1_1") (pintype "passive"))
    )
    (net (code "63") (name "PRG0_IEP0_EDC_LATCH_IN0") (class "Default")
      (node (ref "R255") (pin "2") (pinfunction "2_2") (pintype "passive"))
    )
    (net (code "64") (name "PRG0_IEP0_EDC_LATCH_IN1") (class "Default")
      (node (ref "R256") (pin "2") (pinfunction "2_2") (pintype "passive"))
    )
    (net (code "65") (name "PRG1_IEP0_EDC_SYNC_OUT0") (class "Default")
      (node (ref "R231") (pin "1") (pinfunction "1_1") (pintype "passive"))
    )
    (net (code "66") (name "PRG1_IEP0_EDC_SYNC_OUT1") (class "Default")
      (node (ref "R226") (pin "1") (pinfunction "1_1") (pintype "passive"))
    )
    (net (code "67") (name "SERDES0_REFCLK0_N") (class "Default")
      (node (ref "R207") (pin "2") (pinfunction "2_2") (pintype "passive"))
      (node (ref "R259") (pin "2") (pinfunction "2_2") (pintype "passive"))
    )
    (net (code "68") (name "SERDES0_REFCLK0_P") (class "Default")
      (node (ref "R206") (pin "2") (pinfunction "2_2") (pintype "passive"))
      (node (ref "R73") (pin "2") (pinfunction "2_2") (pintype "passive"))
    )
    (net (code "69") (name "SFP0_PHY_25M") (class "Default")
      (node (ref "R215") (pin "2") (pinfunction "2_2") (pintype "passive"))
      (node (ref "R218") (pin "2") (pinfunction "2_2") (pintype "passive"))
    )
    (net (code "70") (name "SFP0_PHY_SYNCE_CLK") (class "Default")
      (node (ref "R208") (pin "1") (pinfunction "1_1") (pintype "passive"))
    )
    (net (code "71") (name "SFP0_PHY_XO") (class "Default")
      (node (ref "R219") (pin "2") (pinfunction "2_2") (pintype "passive"))
    )
    (net (code "72") (name "SFP1_PHY_25M") (class "Default")
      (node (ref "R217") (pin "2") (pinfunction "2_2") (pintype "passive"))
      (node (ref "R228") (pin "2") (pinfunction "2_2") (pintype "passive"))
    )
    (net (code "73") (name "SFP1_PHY_SYNCE_CLK") (class "Default")
      (node (ref "R209") (pin "1") (pinfunction "1_1") (pintype "passive"))
    )
    (net (code "74") (name "SFP1_PHY_XO") (class "Default")
      (node (ref "R229") (pin "2") (pinfunction "2_2") (pintype "passive"))
    )
    (net (code "75") (name "SFP2_PHY_25M") (class "Default")
      (node (ref "R221") (pin "2") (pinfunction "2_2") (pintype "passive"))
      (node (ref "R238") (pin "2") (pinfunction "2_2") (pintype "passive"))
    )
    (net (code "76") (name "SFP2_PHY_SYNCE_CLK") (class "Default")
      (node (ref "R210") (pin "1") (pinfunction "1_1") (pintype "passive"))
    )
    (net (code "77") (name "SFP2_PHY_XO") (class "Default")
      (node (ref "R239") (pin "2") (pinfunction "2_2") (pintype "passive"))
    )
    (net (code "78") (name "TIMER_IO0") (class "Default")
      (node (ref "R237") (pin "1") (pinfunction "1_1") (pintype "passive"))
    )
    (net (code "79") (name "TIMER_IO1") (class "Default")
      (node (ref "R230") (pin "1") (pinfunction "1_1") (pintype "passive"))
    )
    (net (code "80") (name "unconnected-(U36-~{CLK}-Pad3)") (class "Default")
      (node (ref "U36") (pin "3") (pinfunction "~{CLK}_3") (pintype "input"))
    )
    (net (code "81") (name "unconnected-(U36-~{Q0}-Pad14)") (class "Default")
      (node (ref "U36") (pin "14") (pinfunction "~{Q0}_14") (pintype "output"))
    )
    (net (code "82") (name "unconnected-(U36-~{Q1}-Pad11)") (class "Default")
      (node (ref "U36") (pin "11") (pinfunction "~{Q1}_11") (pintype "output"))
    )
    (net (code "83") (name "unconnected-(U36-~{Q2}-Pad9)") (class "Default")
      (node (ref "U36") (pin "9") (pinfunction "~{Q2}_9") (pintype "output"))
    )
    (net (code "84") (name "unconnected-(U36-~{Q3}-Pad6)") (class "Default")
      (node (ref "U36") (pin "6") (pinfunction "~{Q3}_6") (pintype "output"))
    )
    (net (code "85") (name "unconnected-(U37-NC-Pad3)") (class "Default")
      (node (ref "U37") (pin "3") (pinfunction "NC_3") (pintype "passive"))
    )
    (net (code "86") (name "unconnected-(U37-S8-Pad9)") (class "Default")
      (node (ref "U37") (pin "9") (pinfunction "S8_9") (pintype "bidirectional"))
    )
  )
)
